# TRACTIAN_microSD.net
KiCad netlist of a schematic drawn in Altium Designer
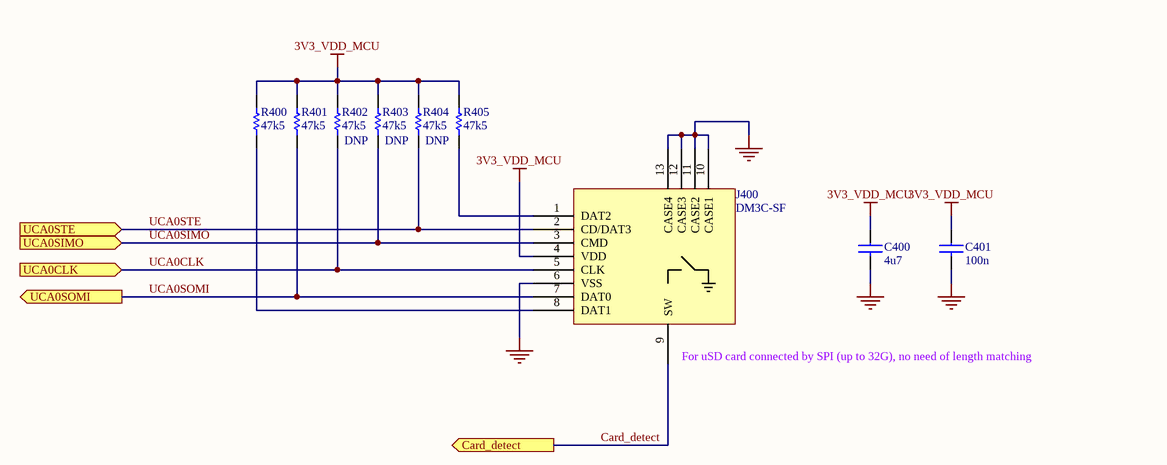
[diagram p0: TRACTIAN_microSD.SchDoc]

(export (version "E")
  (design (tool "Eeschema 10.0.6"))
  (components
    (comp (ref "C400")
      (value "4u7")
      (footprint "C0402")
      (description "CAP CER 4.7UF 10V 20% X5R 0402")
      (fields
        (field (name "MANUFACTURER") "TDK Corporation")
        (field (name "MANUFACTURER PART NUMBER") "C1005X5R1A475M")
        (field (name ".CHECKED PCB") "RF")
        (field (name ".CHECKED SCH") "RF")
      )
      (libsource (lib "TRACTIAN-HW-Challenge") (part "C1005X5R1A475M"))
    )
    (comp (ref "C401")
      (value "100n")
      (footprint "C0402")
      (description "CAP CER .10UF 50V X5R 10% 0402")
      (fields
        (field (name "MANUFACTURER") "TDK Corporation")
        (field (name "MANUFACTURER PART NUMBER") "C1005X5R1H104K")
      )
      (libsource (lib "TRACTIAN-HW-Challenge") (part "C1005X5R1H104K"))
    )
    (comp (ref "J400")
      (value "DM3C-SF")
      (footprint "uSD_DM3CS")
      (description "CONN MICRO SD R/A HING TYPE SMD")
      (fields
        (field (name "MANUFACTURER") "Hirose Electric Co Ltd")
        (field (name ".CREATOR") "MM")
        (field (name ".CHECKED PCB") "MM")
        (field (name ".CHECKED SCH") "MM")
      )
      (libsource (lib "TRACTIAN-HW-Challenge") (part "DM3C-SF"))
    )
    (comp (ref "R400")
      (value "47k5")
      (footprint "R0402")
      (description "RES 47.5K OHM 1/16W 1% 0402 SMD")
      (fields
        (field (name "MANUFACTURER") "Yageo")
        (field (name "MANUFACTURER PART NUMBER") "RC0402FR-0747K5L")
        (field (name ".CHECKED PCB") "RF")
        (field (name ".CHECKED SCH") "RF")
      )
      (libsource (lib "TRACTIAN-HW-Challenge") (part "RC0402FR-0747K5L"))
    )
    (comp (ref "R401")
      (value "47k5")
      (footprint "R0402")
      (description "RES 47.5K OHM 1/16W 1% 0402 SMD")
      (fields
        (field (name "MANUFACTURER") "Yageo")
        (field (name "MANUFACTURER PART NUMBER") "RC0402FR-0747K5L")
        (field (name ".CHECKED PCB") "RF")
        (field (name ".CHECKED SCH") "RF")
      )
      (libsource (lib "TRACTIAN-HW-Challenge") (part "RC0402FR-0747K5L"))
    )
    (comp (ref "R402")
      (value "47k5")
      (footprint "R0402")
      (description "RES 47.5K OHM 1/16W 1% 0402 SMD")
      (fields
        (field (name "MANUFACTURER") "Yageo")
        (field (name "MANUFACTURER PART NUMBER") "RC0402FR-0747K5L")
        (field (name "ASSEMBLY") "DNP")
        (field (name ".CHECKED PCB") "RF")
        (field (name ".CHECKED SCH") "RF")
      )
      (libsource (lib "TRACTIAN-HW-Challenge") (part "RC0402FR-0747K5L"))
    )
    (comp (ref "R403")
      (value "47k5")
      (footprint "R0402")
      (description "RES 47.5K OHM 1/16W 1% 0402 SMD")
      (fields
        (field (name "MANUFACTURER") "Yageo")
        (field (name "MANUFACTURER PART NUMBER") "RC0402FR-0747K5L")
        (field (name "ASSEMBLY") "DNP")
        (field (name ".CHECKED PCB") "RF")
        (field (name ".CHECKED SCH") "RF")
      )
      (libsource (lib "TRACTIAN-HW-Challenge") (part "RC0402FR-0747K5L"))
    )
    (comp (ref "R404")
      (value "47k5")
      (footprint "R0402")
      (description "RES 47.5K OHM 1/16W 1% 0402 SMD")
      (fields
        (field (name "MANUFACTURER") "Yageo")
        (field (name "MANUFACTURER PART NUMBER") "RC0402FR-0747K5L")
        (field (name "ASSEMBLY") "DNP")
        (field (name ".CHECKED PCB") "RF")
        (field (name ".CHECKED SCH") "RF")
      )
      (libsource (lib "TRACTIAN-HW-Challenge") (part "RC0402FR-0747K5L"))
    )
    (comp (ref "R405")
      (value "47k5")
      (footprint "R0402")
      (description "RES 47.5K OHM 1/16W 1% 0402 SMD")
      (fields
        (field (name "MANUFACTURER") "Yageo")
        (field (name "MANUFACTURER PART NUMBER") "RC0402FR-0747K5L")
        (field (name ".CHECKED PCB") "RF")
        (field (name ".CHECKED SCH") "RF")
      )
      (libsource (lib "TRACTIAN-HW-Challenge") (part "RC0402FR-0747K5L"))
    )
  )
  (nets
    (net (code "1") (name "/Card_detect") (class "Default")
      (node (ref "J400") (pin "9") (pinfunction "SW_9") (pintype "passive"))
    )
    (net (code "2") (name "/UCA0CLK") (class "Default")
      (node (ref "J400") (pin "5") (pinfunction "CLK_5") (pintype "passive"))
      (node (ref "R402") (pin "1") (pinfunction "1_1") (pintype "passive"))
    )
    (net (code "3") (name "/UCA0SIMO") (class "Default")
      (node (ref "J400") (pin "3") (pinfunction "CMD_3") (pintype "passive"))
      (node (ref "R403") (pin "1") (pinfunction "1_1") (pintype "passive"))
    )
    (net (code "4") (name "/UCA0SOMI") (class "Default")
      (node (ref "J400") (pin "7") (pinfunction "DAT0_7") (pintype "passive"))
      (node (ref "R401") (pin "1") (pinfunction "1_1") (pintype "passive"))
    )
    (net (code "5") (name "/UCA0STE") (class "Default")
      (node (ref "J400") (pin "2") (pinfunction "CD/DAT3_2") (pintype "passive"))
      (node (ref "R404") (pin "1") (pinfunction "1_1") (pintype "passive"))
    )
    (net (code "6") (name "3V3_VDD_MCU") (class "Default")
      (node (ref "C400") (pin "1") (pinfunction "1_1") (pintype "passive"))
      (node (ref "C401") (pin "1") (pinfunction "1_1") (pintype "passive"))
      (node (ref "J400") (pin "4") (pinfunction "VDD_4") (pintype "passive"))
      (node (ref "R400") (pin "2") (pinfunction "2_2") (pintype "passive"))
      (node (ref "R401") (pin "2") (pinfunction "2_2") (pintype "passive"))
      (node (ref "R402") (pin "2") (pinfunction "2_2") (pintype "passive"))
      (node (ref "R403") (pin "2") (pinfunction "2_2") (pintype "passive"))
      (node (ref "R404") (pin "2") (pinfunction "2_2") (pintype "passive"))
      (node (ref "R405") (pin "2") (pinfunction "2_2") (pintype "passive"))
    )
    (net (code "7") (name "GND") (class "Default")
      (node (ref "C400") (pin "2") (pinfunction "2_2") (pintype "passive"))
      (node (ref "C401") (pin "2") (pinfunction "2_2") (pintype "passive"))
      (node (ref "J400") (pin "10") (pinfunction "CASE1_10") (pintype "passive"))
      (node (ref "J400") (pin "11") (pinfunction "CASE2_11") (pintype "passive"))
      (node (ref "J400") (pin "12") (pinfunction "CASE3_12") (pintype "passive"))
      (node (ref "J400") (pin "13") (pinfunction "CASE4_13") (pintype "passive"))
      (node (ref "J400") (pin "6") (pinfunction "VSS_6") (pintype "passive"))
    )
    (net (code "8") (name "Net-(J400-DAT1)") (class "Default")
      (node (ref "J400") (pin "8") (pinfunction "DAT1_8") (pintype "passive"))
      (node (ref "R400") (pin "1") (pinfunction "1_1") (pintype "passive"))
    )
    (net (code "9") (name "Net-(J400-DAT2)") (class "Default")
      (node (ref "J400") (pin "1") (pinfunction "DAT2_1") (pintype "passive"))
      (node (ref "R405") (pin "1") (pinfunction "1_1") (pintype "passive"))
    )
  )
)
